# Power_Supply.net
KiCad netlist of a schematic drawn in Altium Designer
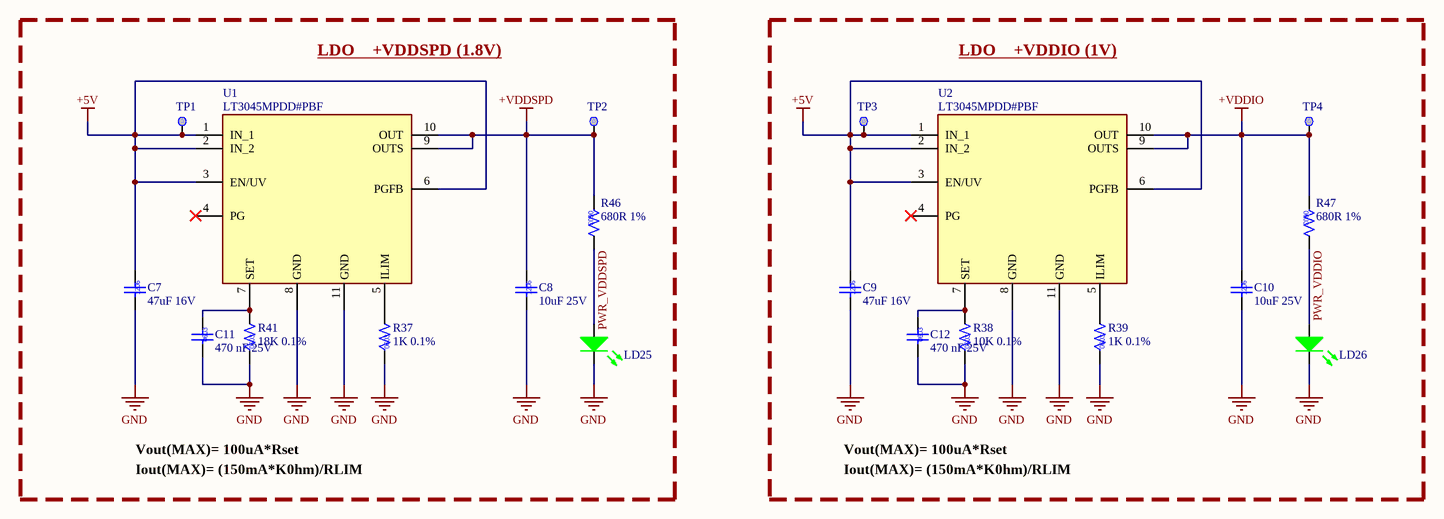
[diagram p0: Power_Supply.SchDoc]

(export (version "E")
  (design (tool "Eeschema 10.0.6"))
  (components
    (comp (ref "C7")
      (value "47uF 16V")
      (footprint "CC/NM 1206")
      (fields
        (field (name "MANUFACTURER") "KYOCERA AVX")
        (field (name "MANUFACTURER PART NUMBER") "1206YD476MAT2A")
      )
      (libsource (lib "DDR5_Nucleo_Shield_Symbols") (part "1206YD476MAT2A"))
    )
    (comp (ref "C8")
      (value "10uF 25V")
      (footprint "CC/NM 1206")
      (description "Condensadores de cerámica multicapa (MLCC- SMD/SMT) CGA 1206 25V 10uF X7R 10% AEC-Q200")
      (fields
        (field (name "MANUFACTURER") "TDK")
        (field (name "MANUFACTURER PART NUMBER") "CGA5L1X7R1E106K160AC")
      )
      (libsource (lib "DDR5_Nucleo_Shield_Symbols") (part "CGA5L1X7R1E106K160AC"))
    )
    (comp (ref "C9")
      (value "47uF 16V")
      (footprint "CC/NM 1206")
      (fields
        (field (name "MANUFACTURER") "KYOCERA AVX")
        (field (name "MANUFACTURER PART NUMBER") "1206YD476MAT2A")
      )
      (libsource (lib "DDR5_Nucleo_Shield_Symbols") (part "1206YD476MAT2A"))
    )
    (comp (ref "C10")
      (value "10uF 25V")
      (footprint "CC/NM 1206")
      (description "Condensadores de cerámica multicapa (MLCC- SMD/SMT) CGA 1206 25V 10uF X7R 10% AEC-Q200")
      (fields
        (field (name "MANUFACTURER") "TDK")
        (field (name "MANUFACTURER PART NUMBER") "CGA5L1X7R1E106K160AC")
      )
      (libsource (lib "DDR5_Nucleo_Shield_Symbols") (part "CGA5L1X7R1E106K160AC"))
    )
    (comp (ref "C11")
      (value "470 nF 25V")
      (footprint "CC/NM 0603")
      (description "Condensadores de cerámica multicapa (MLCC- SMD/SMT) 0201 4VDC 0.47uF 20% X6S 0.3mm")
      (fields
        (field (name "MANUFACTURER") "TDK")
        (field (name "MANUFACTURER PART NUMBER") "C0603X6S0G474M030BC")
      )
      (libsource (lib "DDR5_Nucleo_Shield_Symbols") (part "C0603X6S0G474M030BC"))
    )
    (comp (ref "C12")
      (value "470 nF 25V")
      (footprint "CC/NM 0603")
      (description "Condensadores de cerámica multicapa (MLCC- SMD/SMT) 0201 4VDC 0.47uF 20% X6S 0.3mm")
      (fields
        (field (name "MANUFACTURER") "TDK")
        (field (name "MANUFACTURER PART NUMBER") "C0603X6S0G474M030BC")
      )
      (libsource (lib "DDR5_Nucleo_Shield_Symbols") (part "C0603X6S0G474M030BC"))
    )
    (comp (ref "LD25")
      (value "APHD1608LCGCK")
      (footprint "LED/0603/GREEN")
      (description "Green Light Emitting Diode")
      (fields (field (name "MANUFACTURER") "Kingbright"))
      (libsource (lib "DDR5_Nucleo_Shield_Symbols") (part "APHD1608LCGCK"))
    )
    (comp (ref "LD26")
      (value "APHD1608LCGCK")
      (footprint "LED/0603/GREEN")
      (description "Green Light Emitting Diode")
      (fields (field (name "MANUFACTURER") "Kingbright"))
      (libsource (lib "DDR5_Nucleo_Shield_Symbols") (part "APHD1608LCGCK"))
    )
    (comp (ref "R37")
      (value "1K 0.1%")
      (footprint "CC/NM 0603")
      (description "Resistores de película fina - SMD TNPW-0603 1K 0.1% T-13 R52")
      (fields
        (field (name "MANUFACTURER") "Vishay")
        (field (name "MANUFACTURER PART NUMBER") "TNPW06031K00BYCN")
      )
      (libsource (lib "DDR5_Nucleo_Shield_Symbols") (part "TNPW06031K00BYCN"))
    )
    (comp (ref "R38")
      (value "10K 0.1%")
      (footprint "CC/NM 0603")
      (description "Thin Film Resistors - SMD 1/10watts 10K .1%")
      (fields
        (field (name "MANUFACTURER") "Bourns")
        (field (name "MANUFACTURER PART NUMBER") "CRT0603-BY-1002ELF")
      )
      (libsource (lib "DDR5_Nucleo_Shield_Symbols") (part "CRT0603-BY-1002ELF"))
    )
    (comp (ref "R39")
      (value "1K 0.1%")
      (footprint "CC/NM 0603")
      (description "Resistores de película fina - SMD TNPW-0603 1K 0.1% T-13 R52")
      (fields
        (field (name "MANUFACTURER") "Vishay")
        (field (name "MANUFACTURER PART NUMBER") "TNPW06031K00BYCN")
      )
      (libsource (lib "DDR5_Nucleo_Shield_Symbols") (part "TNPW06031K00BYCN"))
    )
    (comp (ref "R41")
      (value "18K 0.1%")
      (footprint "CC/NM 0603")
      (description "Resistencia SMD de Tipo Chip, 20 kohm, ± 0.1%, 125 mW, 0603 [Métrica 1608], Película Delgada")
      (fields
        (field (name "MANUFACTURER") "Vishay")
        (field (name "MANUFACTURER PART NUMBER") "TNPW060318K0BYCN")
      )
      (libsource (lib "DDR5_Nucleo_Shield_Symbols") (part "TNPW060318K0BYCN"))
    )
    (comp (ref "R46")
      (value "680R 1%")
      (footprint "CC/NM 0603")
      (description "Resistores de película gruesa - SMD 680 ohm 1%")
      (fields
        (field (name "MANUFACTURER") "BOURNS")
        (field (name "MANUFACTURER PART NUMBER") "CR0603-FX-6800ELF")
      )
      (libsource (lib "DDR5_Nucleo_Shield_Symbols") (part "CR0603-FX-6800ELF"))
    )
    (comp (ref "R47")
      (value "680R 1%")
      (footprint "CC/NM 0603")
      (description "Resistores de película gruesa - SMD 680 ohm 1%")
      (fields
        (field (name "MANUFACTURER") "BOURNS")
        (field (name "MANUFACTURER PART NUMBER") "CR0603-FX-6800ELF")
      )
      (libsource (lib "DDR5_Nucleo_Shield_Symbols") (part "CR0603-FX-6800ELF"))
    )
    (comp (ref "TP1")
      (value "Test Point")
      (footprint "TP_SMD_1MM")
      (description "Test Point 1mm")
      (fields
        (field (name "INTERNAL_PART_NUMBER") "MCD-00074")
        (field (name "MANUFACTURER_PART_NUMBER") "n/a")
      )
      (libsource (lib "DDR5_Nucleo_Shield_Symbols") (part "Test_Point_1mm"))
    )
    (comp (ref "TP2")
      (value "Test Point")
      (footprint "TP_SMD_1MM")
      (description "Test Point 1mm")
      (fields
        (field (name "INTERNAL_PART_NUMBER") "MCD-00074")
        (field (name "MANUFACTURER_PART_NUMBER") "n/a")
      )
      (libsource (lib "DDR5_Nucleo_Shield_Symbols") (part "Test_Point_1mm"))
    )
    (comp (ref "TP3")
      (value "Test Point")
      (footprint "TP_SMD_1MM")
      (description "Test Point 1mm")
      (fields
        (field (name "INTERNAL_PART_NUMBER") "MCD-00074")
        (field (name "MANUFACTURER_PART_NUMBER") "n/a")
      )
      (libsource (lib "DDR5_Nucleo_Shield_Symbols") (part "Test_Point_1mm"))
    )
    (comp (ref "TP4")
      (value "Test Point")
      (footprint "TP_SMD_1MM")
      (description "Test Point 1mm")
      (fields
        (field (name "INTERNAL_PART_NUMBER") "MCD-00074")
        (field (name "MANUFACTURER_PART_NUMBER") "n/a")
      )
      (libsource (lib "DDR5_Nucleo_Shield_Symbols") (part "Test_Point_1mm"))
    )
    (comp (ref "U1")
      (value "LT3045MPDD#PBF")
      (footprint "SON50P300X300X80-11N")
      (description "20V, 500mA, Ultralow Noise, Ultrahigh PSRR Linear Regulator")
      (fields (field (name "MANUFACTURER") "Analog Devices"))
      (libsource (lib "DDR5_Nucleo_Shield_Symbols") (part "LT3045MPDD#PBF"))
    )
    (comp (ref "U2")
      (value "LT3045MPDD#PBF")
      (footprint "SON50P300X300X80-11N")
      (description "20V, 500mA, Ultralow Noise, Ultrahigh PSRR Linear Regulator")
      (fields (field (name "MANUFACTURER") "Analog Devices"))
      (libsource (lib "DDR5_Nucleo_Shield_Symbols") (part "LT3045MPDD#PBF"))
    )
  )
  (nets
    (net (code "1") (name "+5V") (class "Default")
      (node (ref "C7") (pin "2") (pinfunction "2_2") (pintype "passive"))
      (node (ref "C9") (pin "2") (pinfunction "2_2") (pintype "passive"))
      (node (ref "TP1") (pin "1") (pinfunction "1_1") (pintype "passive"))
      (node (ref "TP3") (pin "1") (pinfunction "1_1") (pintype "passive"))
      (node (ref "U1") (pin "1") (pinfunction "IN_1_1") (pintype "power_in"))
      (node (ref "U1") (pin "2") (pinfunction "IN_2_2") (pintype "power_in"))
      (node (ref "U1") (pin "3") (pinfunction "EN/UV_3") (pintype "passive"))
      (node (ref "U1") (pin "6") (pinfunction "PGFB_6") (pintype "passive"))
      (node (ref "U2") (pin "1") (pinfunction "IN_1_1") (pintype "power_in"))
      (node (ref "U2") (pin "2") (pinfunction "IN_2_2") (pintype "power_in"))
      (node (ref "U2") (pin "3") (pinfunction "EN/UV_3") (pintype "passive"))
      (node (ref "U2") (pin "6") (pinfunction "PGFB_6") (pintype "passive"))
    )
    (net (code "2") (name "+VDDIO") (class "Default")
      (node (ref "C10") (pin "2") (pinfunction "2_2") (pintype "passive"))
      (node (ref "R47") (pin "1") (pinfunction "1_1") (pintype "passive"))
      (node (ref "TP4") (pin "1") (pinfunction "1_1") (pintype "passive"))
      (node (ref "U2") (pin "10") (pinfunction "OUT_10") (pintype "passive"))
      (node (ref "U2") (pin "9") (pinfunction "OUTS_9") (pintype "passive"))
    )
    (net (code "3") (name "+VDDSPD") (class "Default")
      (node (ref "C8") (pin "2") (pinfunction "2_2") (pintype "passive"))
      (node (ref "R46") (pin "1") (pinfunction "1_1") (pintype "passive"))
      (node (ref "TP2") (pin "1") (pinfunction "1_1") (pintype "passive"))
      (node (ref "U1") (pin "10") (pinfunction "OUT_10") (pintype "passive"))
      (node (ref "U1") (pin "9") (pinfunction "OUTS_9") (pintype "passive"))
    )
    (net (code "4") (name "/PWR_VDDIO") (class "Default")
      (node (ref "LD26") (pin "1") (pinfunction "A_1") (pintype "passive"))
      (node (ref "R47") (pin "2") (pinfunction "2_2") (pintype "passive"))
    )
    (net (code "5") (name "/PWR_VDDSPD") (class "Default")
      (node (ref "LD25") (pin "1") (pinfunction "A_1") (pintype "passive"))
      (node (ref "R46") (pin "2") (pinfunction "2_2") (pintype "passive"))
    )
    (net (code "6") (name "GND") (class "Default")
      (node (ref "C10") (pin "1") (pinfunction "1_1") (pintype "passive"))
      (node (ref "C11") (pin "1") (pinfunction "1_1") (pintype "passive"))
      (node (ref "C12") (pin "1") (pinfunction "1_1") (pintype "passive"))
      (node (ref "C7") (pin "1") (pinfunction "1_1") (pintype "passive"))
      (node (ref "C8") (pin "1") (pinfunction "1_1") (pintype "passive"))
      (node (ref "C9") (pin "1") (pinfunction "1_1") (pintype "passive"))
      (node (ref "LD25") (pin "2") (pinfunction "K_2") (pintype "passive"))
      (node (ref "LD26") (pin "2") (pinfunction "K_2") (pintype "passive"))
      (node (ref "R37") (pin "1") (pinfunction "1_1") (pintype "passive"))
      (node (ref "R38") (pin "1") (pinfunction "1_1") (pintype "passive"))
      (node (ref "R39") (pin "1") (pinfunction "1_1") (pintype "passive"))
      (node (ref "R41") (pin "1") (pinfunction "1_1") (pintype "passive"))
      (node (ref "U1") (pin "11") (pinfunction "GND_11") (pintype "power_in"))
      (node (ref "U1") (pin "8") (pinfunction "GND_8") (pintype "power_in"))
      (node (ref "U2") (pin "11") (pinfunction "GND_11") (pintype "power_in"))
      (node (ref "U2") (pin "8") (pinfunction "GND_8") (pintype "power_in"))
    )
    (net (code "7") (name "Net-(U1-ILIM)") (class "Default")
      (node (ref "R37") (pin "2") (pinfunction "2_2") (pintype "passive"))
      (node (ref "U1") (pin "5") (pinfunction "ILIM_5") (pintype "passive"))
    )
    (net (code "8") (name "Net-(U1-SET)") (class "Default")
      (node (ref "C11") (pin "2") (pinfunction "2_2") (pintype "passive"))
      (node (ref "R41") (pin "2") (pinfunction "2_2") (pintype "passive"))
      (node (ref "U1") (pin "7") (pinfunction "SET_7") (pintype "passive"))
    )
    (net (code "9") (name "Net-(U2-ILIM)") (class "Default")
      (node (ref "R39") (pin "2") (pinfunction "2_2") (pintype "passive"))
      (node (ref "U2") (pin "5") (pinfunction "ILIM_5") (pintype "passive"))
    )
    (net (code "10") (name "Net-(U2-SET)") (class "Default")
      (node (ref "C12") (pin "2") (pinfunction "2_2") (pintype "passive"))
      (node (ref "R38") (pin "2") (pinfunction "2_2") (pintype "passive"))
      (node (ref "U2") (pin "7") (pinfunction "SET_7") (pintype "passive"))
    )
    (net (code "11") (name "unconnected-(U1-PG-Pad4)") (class "Default")
      (node (ref "U1") (pin "4") (pinfunction "PG_4") (pintype "passive+no_connect"))
    )
    (net (code "12") (name "unconnected-(U2-PG-Pad4)") (class "Default")
      (node (ref "U2") (pin "4") (pinfunction "PG_4") (pintype "passive+no_connect"))
    )
  )
)
